# Charging_PCB.net
KiCad netlist of a schematic drawn in Altium Designer
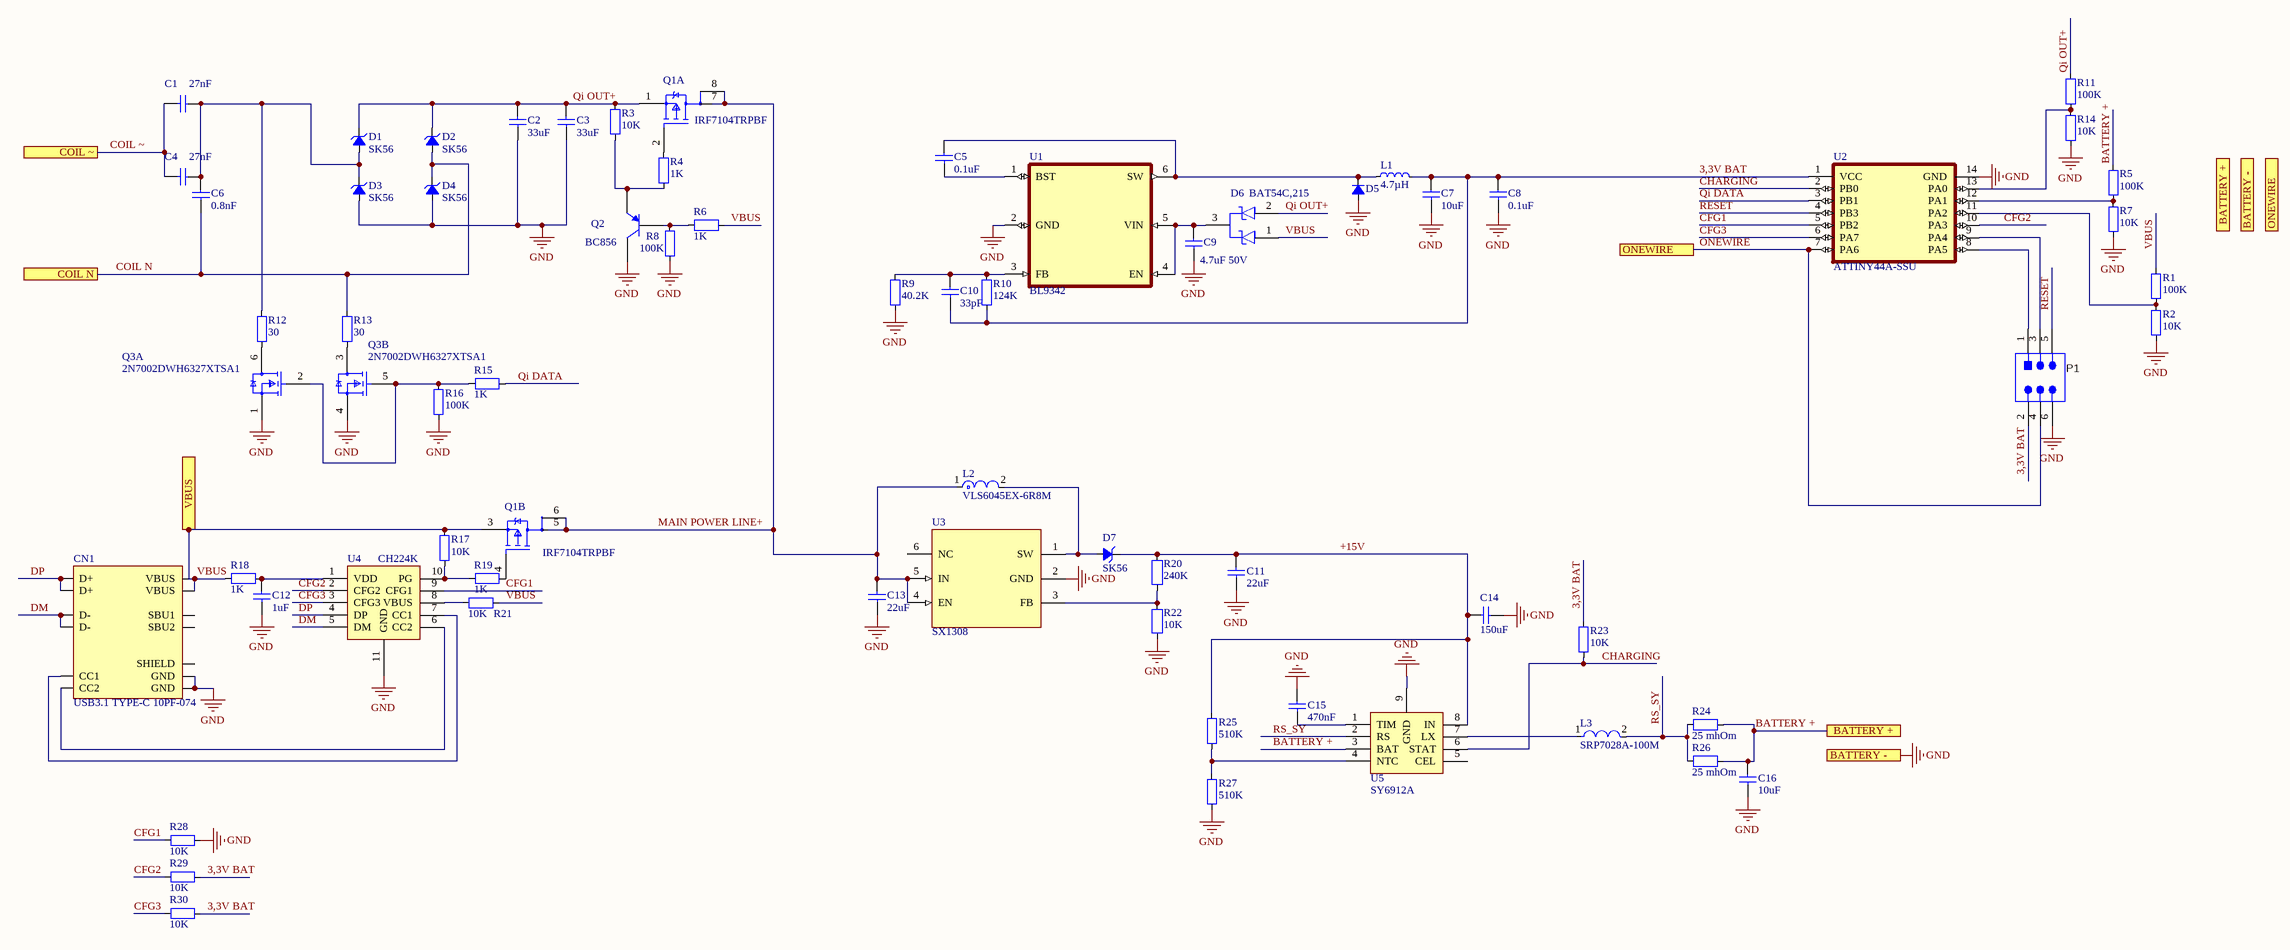
[diagram p0: Charging_PCB.SchDoc]

(export (version "E")
  (design (tool "Eeschema 10.0.6"))
  (components
    (comp (ref "C1") (value "27nF") (footprint "1206") (libsource (lib "V_NB-IoT_3.1") (part "CAP")))
    (comp (ref "C2") (value "33uF") (footprint "1206") (libsource (lib "V_NB-IoT_3.1") (part "CAP")))
    (comp (ref "C3") (value "33uF") (footprint "1206") (libsource (lib "V_NB-IoT_3.1") (part "CAP")))
    (comp (ref "C4") (value "27nF") (footprint "1206") (libsource (lib "V_NB-IoT_3.1") (part "CAP")))
    (comp (ref "C5") (value "0.1uF") (footprint "R0603") (libsource (lib "V_NB-IoT_3.1") (part "CAP")))
    (comp (ref "C6") (value "0.8nF") (footprint "1206") (libsource (lib "V_NB-IoT_3.1") (part "CAP")))
    (comp (ref "C7") (value "10uF") (footprint "C0805") (libsource (lib "V_NB-IoT_3.1") (part "CAP")))
    (comp (ref "C8") (value "0.1uF") (footprint "R0603") (libsource (lib "V_NB-IoT_3.1") (part "CAP")))
    (comp (ref "C9") (value "4.7uF 50V") (footprint "C0805") (libsource (lib "V_NB-IoT_3.1") (part "CAP")))
    (comp (ref "C10") (value "33pF") (footprint "R0603") (libsource (lib "V_NB-IoT_3.1") (part "CAP")))
    (comp (ref "C11") (value "22uF") (footprint "1206") (libsource (lib "V_NB-IoT_3.1") (part "CAP")))
    (comp (ref "C12") (value "1uF") (footprint "C0805") (libsource (lib "V_NB-IoT_3.1") (part "CAP")))
    (comp (ref "C13") (value "22uF") (footprint "1206") (libsource (lib "V_NB-IoT_3.1") (part "CAP")))
    (comp (ref "C14") (value "150uF") (footprint "1206") (libsource (lib "V_NB-IoT_3.1") (part "CAP")))
    (comp (ref "C15") (value "470nF") (footprint "R0603") (libsource (lib "V_NB-IoT_3.1") (part "CAP")))
    (comp (ref "C16") (value "10uF") (footprint "1206") (libsource (lib "V_NB-IoT_3.1") (part "CAP")))
    (comp (ref "CN1")
      (value "USB3.1 TYPE-C 10PF-074")
      (footprint "V_NB_IoT_3.1:USB3.1 TYPE-C 10PF-074")
      (description "XKB Connectivity USB-C Connector")
      (libsource (lib "V_NB-IoT_3.1") (part "USB3.1 TYPE-C 10PF-074"))
    )
    (comp (ref "D1")
      (value "SK56")
      (footprint "DO-214AA(SMB)")
      (description "DO-214 Diode")
      (fields (field (name "MANUFACTURER PART NUMBER") "China"))
      (libsource (lib "V_NB-IoT_3.1") (part "DIODE_DO-214"))
    )
    (comp (ref "D2")
      (value "SK56")
      (footprint "DO-214AA(SMB)")
      (description "DO-214 Diode")
      (fields (field (name "MANUFACTURER PART NUMBER") "China"))
      (libsource (lib "V_NB-IoT_3.1") (part "DIODE_DO-214"))
    )
    (comp (ref "D3")
      (value "SK56")
      (footprint "DO-214AA(SMB)")
      (description "DO-214 Diode")
      (fields (field (name "MANUFACTURER PART NUMBER") "China"))
      (libsource (lib "V_NB-IoT_3.1") (part "DIODE_DO-214"))
    )
    (comp (ref "D4")
      (value "SK56")
      (footprint "DO-214AA(SMB)")
      (description "DO-214 Diode")
      (fields (field (name "MANUFACTURER PART NUMBER") "China"))
      (libsource (lib "V_NB-IoT_3.1") (part "DIODE_DO-214"))
    )
    (comp (ref "D5")
      (value "~")
      (footprint "SOD-123")
      (description "Schottky diode SOD123")
      (libsource (lib "V_NB-IoT_3.1") (part "Diode_SOD123"))
    )
    (comp (ref "D6")
      (value "BAT54C,215")
      (footprint "SOT-23")
      (description "DIODE ARRAY SCHOTTKY 30V SOT23")
      (fields
        (field (name "MANUFACTURER") "Nexperia")
        (field (name "OCTOPART") "https://octopart.com/bat54c%2C215-nexperia-78738945")
      )
      (libsource (lib "V_NB-IoT_3.1") (part "BAT54C"))
    )
    (comp (ref "D7")
      (value "SK56")
      (footprint "DO-214AA(SMB)")
      (description "DO-214 Diode")
      (fields (field (name "MANUFACTURER PART NUMBER") "China"))
      (libsource (lib "V_NB-IoT_3.1") (part "DIODE_DO-214"))
    )
    (comp (ref "L1")
      (value "4.7µH")
      (footprint "INDC1608X06L")
      (description "Inductor, SMD")
      (fields
        (field (name "PART NUMBER") "L0603-10µ")
        (field (name "MANUFACTURER") "Taiyo Yuden")
        (field (name "PUBLISHER") "Nordic Semiconductor")
      )
      (libsource (lib "V_NB-IoT_3.1") (part "IND_1"))
    )
    (comp (ref "L2")
      (value "VLS6045EX-6R8M")
      (footprint "FP-VLS6045EX-100M-MFG")
      (description "FIXED IND  SMD")
      (fields (field (name "TOLERANCE") "20%"))
      (libsource (lib "V_NB-IoT_3.1") (part "VLS6045EX"))
    )
    (comp (ref "L3")
      (value "SRP7028A-100M")
      (footprint "INDUCT_7028")
      (description "FIXED IND")
      (fields (field (name "TOLERANCE") "20%") (field (name "MANUFACTURER") "Panasonic"))
      (libsource (lib "V_NB-IoT_3.1") (part "IND_SRP7028A"))
    )
    (comp (ref "P1")
      (value "TSW-103-07-G-D")
      (footprint "SMTC-TSW-103-07-G-D_V")
      (fields (field (name "MANUFACTURER") "Samtec-Inc.") (field (name "MANUFACTURER_1") "Samtec"))
      (libsource (lib "V_NB-IoT_3.1") (part "CMP-2000-07329-1"))
    )
    (comp (ref "Q1")
      (value "IRF7104TRPBF")
      (footprint "SO8")
      (description "MOSFET 2P-CH 20V 2.3A 8-SOIC")
      (libsource (lib "V_NB-IoT_3.1") (part "IRF7104TRPBF"))
    )
    (comp (ref "Q2")
      (value "BC856")
      (footprint "SOT-23")
      (description "PNP General Purpose Transistor, 65 V, -65 to 150 degC, 3-Pin SOT23, RoHS")
      (fields (field (name "MANUFACTURER") "NXP"))
      (libsource (lib "V_NB-IoT_3.1") (part "BC856"))
    )
    (comp (ref "Q3")
      (value "2N7002DWH6327XTSA1")
      (footprint "SOT363-IPC_A")
      (description "MOSFET 2N-CH 60V 0.3A SOT363")
      (libsource (lib "V_NB-IoT_3.1") (part "WM06DN03D"))
    )
    (comp (ref "R1")
      (value "100K")
      (footprint "R0603")
      (description "Resistor SMD")
      (libsource (lib "V_NB-IoT_3.1") (part "RES SMD UNI"))
    )
    (comp (ref "R2")
      (value "10K")
      (footprint "R0603")
      (description "Resistor SMD")
      (libsource (lib "V_NB-IoT_3.1") (part "RES SMD UNI"))
    )
    (comp (ref "R3")
      (value "10K")
      (footprint "R0603")
      (description "Resistor SMD")
      (libsource (lib "V_NB-IoT_3.1") (part "RES SMD UNI"))
    )
    (comp (ref "R4")
      (value "1K")
      (footprint "R0603")
      (description "Resistor SMD")
      (libsource (lib "V_NB-IoT_3.1") (part "RES SMD UNI"))
    )
    (comp (ref "R5")
      (value "100K")
      (footprint "R0603")
      (description "Resistor SMD")
      (libsource (lib "V_NB-IoT_3.1") (part "RES SMD UNI"))
    )
    (comp (ref "R6")
      (value "1K")
      (footprint "R0603")
      (description "Resistor SMD")
      (libsource (lib "V_NB-IoT_3.1") (part "RES SMD UNI"))
    )
    (comp (ref "R7")
      (value "10K")
      (footprint "R0603")
      (description "Resistor SMD")
      (libsource (lib "V_NB-IoT_3.1") (part "RES SMD UNI"))
    )
    (comp (ref "R8")
      (value "100K")
      (footprint "R0603")
      (description "Resistor SMD")
      (libsource (lib "V_NB-IoT_3.1") (part "RES SMD UNI"))
    )
    (comp (ref "R9")
      (value "40.2K")
      (footprint "R0603")
      (description "Resistor SMD")
      (libsource (lib "V_NB-IoT_3.1") (part "RES SMD UNI"))
    )
    (comp (ref "R10")
      (value "124K")
      (footprint "R0603")
      (description "Resistor SMD")
      (libsource (lib "V_NB-IoT_3.1") (part "RES SMD UNI"))
    )
    (comp (ref "R11")
      (value "100K")
      (footprint "R0603")
      (description "Resistor SMD")
      (libsource (lib "V_NB-IoT_3.1") (part "RES SMD UNI"))
    )
    (comp (ref "R12")
      (value "30")
      (footprint "R0603")
      (description "Resistor SMD")
      (libsource (lib "V_NB-IoT_3.1") (part "RES SMD UNI"))
    )
    (comp (ref "R13")
      (value "30")
      (footprint "R0603")
      (description "Resistor SMD")
      (libsource (lib "V_NB-IoT_3.1") (part "RES SMD UNI"))
    )
    (comp (ref "R14")
      (value "10K")
      (footprint "R0603")
      (description "Resistor SMD")
      (libsource (lib "V_NB-IoT_3.1") (part "RES SMD UNI"))
    )
    (comp (ref "R15")
      (value "1K")
      (footprint "R0603")
      (description "Resistor SMD")
      (libsource (lib "V_NB-IoT_3.1") (part "RES SMD UNI"))
    )
    (comp (ref "R16")
      (value "100K")
      (footprint "R0603")
      (description "Resistor SMD")
      (libsource (lib "V_NB-IoT_3.1") (part "RES SMD UNI"))
    )
    (comp (ref "R17")
      (value "10K")
      (footprint "R0603")
      (description "Resistor SMD")
      (libsource (lib "V_NB-IoT_3.1") (part "RES SMD UNI"))
    )
    (comp (ref "R18")
      (value "1K")
      (footprint "R0603")
      (description "Resistor SMD")
      (libsource (lib "V_NB-IoT_3.1") (part "RES SMD UNI"))
    )
    (comp (ref "R19")
      (value "1K")
      (footprint "R0603")
      (description "Resistor SMD")
      (libsource (lib "V_NB-IoT_3.1") (part "RES SMD UNI"))
    )
    (comp (ref "R20")
      (value "240K")
      (footprint "R0603")
      (description "Resistor SMD")
      (libsource (lib "V_NB-IoT_3.1") (part "RES SMD UNI"))
    )
    (comp (ref "R21")
      (value "10K")
      (footprint "R0603")
      (description "Resistor SMD")
      (libsource (lib "V_NB-IoT_3.1") (part "RES SMD UNI"))
    )
    (comp (ref "R22")
      (value "10K")
      (footprint "R0603")
      (description "Resistor SMD")
      (libsource (lib "V_NB-IoT_3.1") (part "RES SMD UNI"))
    )
    (comp (ref "R23")
      (value "10K")
      (footprint "R0603")
      (description "Resistor SMD")
      (libsource (lib "V_NB-IoT_3.1") (part "RES SMD UNI"))
    )
    (comp (ref "R24")
      (value "25 mhOm")
      (footprint "1206")
      (description "Resistor SMD")
      (libsource (lib "V_NB-IoT_3.1") (part "RES SMD UNI"))
    )
    (comp (ref "R25")
      (value "510K")
      (footprint "R0603")
      (description "Resistor SMD")
      (libsource (lib "V_NB-IoT_3.1") (part "RES SMD UNI"))
    )
    (comp (ref "R26")
      (value "25 mhOm")
      (footprint "1206")
      (description "Resistor SMD")
      (libsource (lib "V_NB-IoT_3.1") (part "RES SMD UNI"))
    )
    (comp (ref "R27")
      (value "510K")
      (footprint "R0603")
      (description "Resistor SMD")
      (libsource (lib "V_NB-IoT_3.1") (part "RES SMD UNI"))
    )
    (comp (ref "R28")
      (value "10K")
      (footprint "R0603")
      (description "Resistor SMD")
      (libsource (lib "V_NB-IoT_3.1") (part "RES SMD UNI"))
    )
    (comp (ref "R29")
      (value "10K")
      (footprint "R0603")
      (description "Resistor SMD")
      (libsource (lib "V_NB-IoT_3.1") (part "RES SMD UNI"))
    )
    (comp (ref "R30")
      (value "10K")
      (footprint "R0603")
      (description "Resistor SMD")
      (libsource (lib "V_NB-IoT_3.1") (part "RES SMD UNI"))
    )
    (comp (ref "U1")
      (value "BL9342")
      (footprint "SOT23-6")
      (fields (field (name "MF") "{'manufacturer': u'Texas Instruments'}"))
      (libsource (lib "V_NB-IoT_3.1") (part "BL9342"))
    )
    (comp (ref "U2")
      (value "ATTINY44A-SSU")
      (footprint "SO14")
      (fields (field (name "MF") "{'manufacturer': u'Microchip'}"))
      (libsource (lib "V_NB-IoT_3.1") (part "ATTINY44A-SSU"))
    )
    (comp (ref "U3")
      (value "SX1308")
      (footprint "SOT23-6")
      (description "IC REG BOOST ADJ 2A TSOT23-6")
      (fields (field (name "MANUFACTURER") "Suosemi"))
      (libsource (lib "V_NB-IoT_3.1") (part "SX1308"))
    )
    (comp (ref "U4")
      (value "CH224K")
      (footprint "ESSOP10")
      (description "IC PD QC USB driver")
      (fields (field (name "MANUFACTURER") "ST") (field (name "MANUFACTURER PART NUMBER") "ST3485EBDR"))
      (libsource (lib "V_NB-IoT_3.1") (part "CH224K"))
    )
    (comp (ref "U5") (value "SY6912A") (footprint "PSOP8") (libsource (lib "V_NB-IoT_3.1") (part "SY6912A")))
  )
  (nets
    (net (code "1") (name "/+15V") (class "Default")
      (node (ref "C11") (pin "2") (pinfunction "2_2") (pintype "passive"))
      (node (ref "C14") (pin "1") (pinfunction "1_1") (pintype "passive"))
      (node (ref "D7") (pin "1") (pinfunction "K_1") (pintype "passive"))
      (node (ref "R20") (pin "1") (pinfunction "1_1") (pintype "passive"))
      (node (ref "R25") (pin "1") (pinfunction "1_1") (pintype "passive"))
      (node (ref "U5") (pin "8") (pinfunction "IN_8") (pintype "passive"))
    )
    (net (code "2") (name "/3,3V BAT") (class "Default")
      (node (ref "C10") (pin "1") (pinfunction "1_1") (pintype "passive"))
      (node (ref "C7") (pin "2") (pinfunction "2_2") (pintype "passive"))
      (node (ref "C8") (pin "2") (pinfunction "2_2") (pintype "passive"))
      (node (ref "L1") (pin "2") (pinfunction "2_2") (pintype "passive"))
      (node (ref "P1") (pin "2") (pinfunction "2_2") (pintype "passive"))
      (node (ref "R10") (pin "1") (pinfunction "1_1") (pintype "passive"))
      (node (ref "R23") (pin "2") (pinfunction "2_2") (pintype "passive"))
      (node (ref "R29") (pin "2") (pinfunction "2_2") (pintype "passive"))
      (node (ref "R30") (pin "2") (pinfunction "2_2") (pintype "passive"))
      (node (ref "U2") (pin "1") (pinfunction "VCC_1") (pintype "power_in"))
    )
    (net (code "3") (name "/BATTERY +") (class "Default")
      (node (ref "C16") (pin "2") (pinfunction "2_2") (pintype "passive"))
      (node (ref "R24") (pin "2") (pinfunction "2_2") (pintype "passive"))
      (node (ref "R26") (pin "2") (pinfunction "2_2") (pintype "passive"))
      (node (ref "R5") (pin "2") (pinfunction "2_2") (pintype "passive"))
      (node (ref "U5") (pin "3") (pinfunction "BAT_3") (pintype "passive"))
    )
    (net (code "4") (name "/CFG1") (class "Default")
      (node (ref "R28") (pin "1") (pinfunction "1_1") (pintype "passive"))
      (node (ref "U2") (pin "5") (pinfunction "PB2_5") (pintype "bidirectional"))
      (node (ref "U4") (pin "9") (pinfunction "CFG1_9") (pintype "power_in"))
    )
    (net (code "5") (name "/CFG2") (class "Default")
      (node (ref "R29") (pin "1") (pinfunction "1_1") (pintype "passive"))
      (node (ref "U2") (pin "10") (pinfunction "PA3_10") (pintype "bidirectional"))
      (node (ref "U4") (pin "2") (pinfunction "CFG2_2") (pintype "power_in"))
    )
    (net (code "6") (name "/CFG3") (class "Default")
      (node (ref "R30") (pin "1") (pinfunction "1_1") (pintype "passive"))
      (node (ref "U2") (pin "6") (pinfunction "PA7_6") (pintype "bidirectional"))
      (node (ref "U4") (pin "3") (pinfunction "CFG3_3") (pintype "power_in"))
    )
    (net (code "7") (name "/CHARGING") (class "Default")
      (node (ref "R23") (pin "1") (pinfunction "1_1") (pintype "passive"))
      (node (ref "U2") (pin "2") (pinfunction "PB0_2") (pintype "bidirectional"))
      (node (ref "U5") (pin "6") (pinfunction "STAT_6") (pintype "passive"))
    )
    (net (code "8") (name "/COIL N") (class "Default")
      (node (ref "C6") (pin "2") (pinfunction "2_2") (pintype "passive"))
      (node (ref "D2") (pin "2") (pinfunction "A_2") (pintype "passive"))
      (node (ref "D4") (pin "1") (pinfunction "K_1") (pintype "passive"))
      (node (ref "R13") (pin "2") (pinfunction "2_2") (pintype "passive"))
    )
    (net (code "9") (name "/COIL ~") (class "Default")
      (node (ref "C1") (pin "2") (pinfunction "2_2") (pintype "passive"))
      (node (ref "C4") (pin "2") (pinfunction "2_2") (pintype "passive"))
    )
    (net (code "10") (name "/DM") (class "Default")
      (node (ref "CN1") (pin "6") (pinfunction "D-_6") (pintype "passive"))
      (node (ref "CN1") (pin "9") (pinfunction "D-_9") (pintype "passive"))
      (node (ref "U4") (pin "5") (pinfunction "DM_5") (pintype "power_in"))
    )
    (net (code "11") (name "/DP") (class "Default")
      (node (ref "CN1") (pin "4") (pinfunction "D+_4") (pintype "passive"))
      (node (ref "CN1") (pin "7") (pinfunction "D+_7") (pintype "passive"))
      (node (ref "U4") (pin "4") (pinfunction "DP_4") (pintype "power_in"))
    )
    (net (code "12") (name "/MAIN POWER LINE+") (class "Default")
      (node (ref "C13") (pin "2") (pinfunction "2_2") (pintype "passive"))
      (node (ref "L2") (pin "1") (pinfunction "1_1") (pintype "passive"))
      (node (ref "Q1") (pin "5") (pinfunction "D2_5") (pintype "passive"))
      (node (ref "Q1") (pin "6") (pinfunction "D2_6") (pintype "passive"))
      (node (ref "Q1") (pin "7") (pinfunction "D1_7") (pintype "passive"))
      (node (ref "Q1") (pin "8") (pinfunction "D1_8") (pintype "passive"))
      (node (ref "U3") (pin "4") (pinfunction "EN_4") (pintype "input"))
      (node (ref "U3") (pin "5") (pinfunction "IN_5") (pintype "input"))
    )
    (net (code "13") (name "/ONEWIRE") (class "Default")
      (node (ref "P1") (pin "4") (pinfunction "4_4") (pintype "passive"))
      (node (ref "U2") (pin "7") (pinfunction "PA6_7") (pintype "bidirectional"))
    )
    (net (code "14") (name "/Qi DATA") (class "Default")
      (node (ref "R15") (pin "2") (pinfunction "2_2") (pintype "passive"))
      (node (ref "U2") (pin "3") (pinfunction "PB1_3") (pintype "bidirectional"))
    )
    (net (code "15") (name "/Qi OUT+") (class "Default")
      (node (ref "C2") (pin "1") (pinfunction "1_1") (pintype "passive"))
      (node (ref "C3") (pin "1") (pinfunction "1_1") (pintype "passive"))
      (node (ref "D1") (pin "1") (pinfunction "K_1") (pintype "passive"))
      (node (ref "D2") (pin "1") (pinfunction "K_1") (pintype "passive"))
      (node (ref "D6") (pin "2") (pinfunction "2_ANODE_2") (pintype "passive"))
      (node (ref "Q1") (pin "1") (pinfunction "S1_1") (pintype "passive"))
      (node (ref "R11") (pin "2") (pinfunction "2_2") (pintype "passive"))
      (node (ref "R3") (pin "2") (pinfunction "2_2") (pintype "passive"))
    )
    (net (code "16") (name "/RESET") (class "Default")
      (node (ref "P1") (pin "5") (pinfunction "5_5") (pintype "passive"))
      (node (ref "U2") (pin "4") (pinfunction "PB3_4") (pintype "bidirectional"))
    )
    (net (code "17") (name "/RS_SY") (class "Default")
      (node (ref "L3") (pin "2") (pinfunction "2_2") (pintype "passive"))
      (node (ref "R24") (pin "1") (pinfunction "1_1") (pintype "passive"))
      (node (ref "R26") (pin "1") (pinfunction "1_1") (pintype "passive"))
      (node (ref "U5") (pin "2") (pinfunction "RS_2") (pintype "passive"))
    )
    (net (code "18") (name "/VBUS") (class "Default")
      (node (ref "CN1") (pin "10") (pinfunction "VBUS_10") (pintype "power_in"))
      (node (ref "CN1") (pin "3") (pinfunction "VBUS_3") (pintype "power_in"))
      (node (ref "D6") (pin "1") (pinfunction "1_ANODE_1") (pintype "passive"))
      (node (ref "Q1") (pin "3") (pinfunction "S2_3") (pintype "passive"))
      (node (ref "R1") (pin "2") (pinfunction "2_2") (pintype "passive"))
      (node (ref "R17") (pin "2") (pinfunction "2_2") (pintype "passive"))
      (node (ref "R18") (pin "1") (pinfunction "1_1") (pintype "passive"))
      (node (ref "R21") (pin "2") (pinfunction "2_2") (pintype "passive"))
      (node (ref "R6") (pin "2") (pinfunction "2_2") (pintype "passive"))
    )
    (net (code "19") (name "GND") (class "Default")
      (node (ref "C11") (pin "1") (pinfunction "1_1") (pintype "passive"))
      (node (ref "C12") (pin "1") (pinfunction "1_1") (pintype "passive"))
      (node (ref "C13") (pin "1") (pinfunction "1_1") (pintype "passive"))
      (node (ref "C14") (pin "2") (pinfunction "2_2") (pintype "passive"))
      (node (ref "C15") (pin "2") (pinfunction "2_2") (pintype "passive"))
      (node (ref "C16") (pin "1") (pinfunction "1_1") (pintype "passive"))
      (node (ref "C2") (pin "2") (pinfunction "2_2") (pintype "passive"))
      (node (ref "C3") (pin "2") (pinfunction "2_2") (pintype "passive"))
      (node (ref "C7") (pin "1") (pinfunction "1_1") (pintype "passive"))
      (node (ref "C8") (pin "1") (pinfunction "1_1") (pintype "passive"))
      (node (ref "C9") (pin "1") (pinfunction "1_1") (pintype "passive"))
      (node (ref "CN1") (pin "1") (pinfunction "GND_1") (pintype "passive"))
      (node (ref "CN1") (pin "12") (pinfunction "GND_12") (pintype "power_in"))
      (node (ref "D3") (pin "2") (pinfunction "A_2") (pintype "passive"))
      (node (ref "D4") (pin "2") (pinfunction "A_2") (pintype "passive"))
      (node (ref "D5") (pin "1") (pinfunction "A_1") (pintype "passive"))
      (node (ref "P1") (pin "6") (pinfunction "6_6") (pintype "passive"))
      (node (ref "Q2") (pin "3") (pinfunction "C_3") (pintype "passive"))
      (node (ref "Q3") (pin "1") (pinfunction "S1_1") (pintype "passive"))
      (node (ref "Q3") (pin "4") (pinfunction "S2_4") (pintype "passive"))
      (node (ref "R14") (pin "1") (pinfunction "1_1") (pintype "passive"))
      (node (ref "R16") (pin "1") (pinfunction "1_1") (pintype "passive"))
      (node (ref "R2") (pin "1") (pinfunction "1_1") (pintype "passive"))
      (node (ref "R22") (pin "1") (pinfunction "1_1") (pintype "passive"))
      (node (ref "R27") (pin "2") (pinfunction "2_2") (pintype "passive"))
      (node (ref "R28") (pin "2") (pinfunction "2_2") (pintype "passive"))
      (node (ref "R7") (pin "1") (pinfunction "1_1") (pintype "passive"))
      (node (ref "R8") (pin "1") (pinfunction "1_1") (pintype "passive"))
      (node (ref "R9") (pin "1") (pinfunction "1_1") (pintype "passive"))
      (node (ref "U1") (pin "2") (pinfunction "GND_2") (pintype "bidirectional"))
      (node (ref "U2") (pin "14") (pinfunction "GND_14") (pintype "power_in"))
      (node (ref "U3") (pin "2") (pinfunction "GND_2") (pintype "passive"))
      (node (ref "U4") (pin "11") (pinfunction "GND_11") (pintype "passive"))
      (node (ref "U5") (pin "9") (pinfunction "GND_9") (pintype "passive"))
    )
    (net (code "20") (name "Net-(CN1-CC1)") (class "Default")
      (node (ref "CN1") (pin "2") (pinfunction "CC1_2") (pintype "passive"))
      (node (ref "U4") (pin "7") (pinfunction "CC1_7") (pintype "power_in"))
    )
    (net (code "21") (name "Net-(CN1-CC2)") (class "Default")
      (node (ref "CN1") (pin "8") (pinfunction "CC2_8") (pintype "passive"))
      (node (ref "U4") (pin "6") (pinfunction "CC2_6") (pintype "power_in"))
    )
    (net (code "22") (name "Net-(D1-A)") (class "Default")
      (node (ref "C1") (pin "1") (pinfunction "1_1") (pintype "passive"))
      (node (ref "C4") (pin "1") (pinfunction "1_1") (pintype "passive"))
      (node (ref "C6") (pin "1") (pinfunction "1_1") (pintype "passive"))
      (node (ref "D1") (pin "2") (pinfunction "A_2") (pintype "passive"))
      (node (ref "D3") (pin "1") (pinfunction "K_1") (pintype "passive"))
      (node (ref "R12") (pin "2") (pinfunction "2_2") (pintype "passive"))
    )
    (net (code "23") (name "Net-(D5-K)") (class "Default")
      (node (ref "C5") (pin "2") (pinfunction "2_2") (pintype "passive"))
      (node (ref "D5") (pin "2") (pinfunction "K_2") (pintype "passive"))
      (node (ref "L1") (pin "1") (pinfunction "1_1") (pintype "passive"))
      (node (ref "U1") (pin "6") (pinfunction "SW_6") (pintype "output"))
    )
    (net (code "24") (name "Net-(D6-COMMON_CATHODE)") (class "Default")
      (node (ref "C9") (pin "2") (pinfunction "2_2") (pintype "passive"))
      (node (ref "D6") (pin "3") (pinfunction "COMMON_CATHODE_3") (pintype "passive"))
      (node (ref "U1") (pin "4") (pinfunction "EN_4") (pintype "input"))
      (node (ref "U1") (pin "5") (pinfunction "VIN_5") (pintype "input"))
    )
    (net (code "25") (name "Net-(D7-A)") (class "Default")
      (node (ref "D7") (pin "2") (pinfunction "A_2") (pintype "passive"))
      (node (ref "L2") (pin "2") (pinfunction "2_2") (pintype "passive"))
      (node (ref "U3") (pin "1") (pinfunction "SW_1") (pintype "power_in"))
    )
    (net (code "26") (name "Net-(Q1A-G1)") (class "Default")
      (node (ref "Q1") (pin "2") (pinfunction "G1_2") (pintype "passive"))
      (node (ref "R4") (pin "2") (pinfunction "2_2") (pintype "passive"))
    )
    (net (code "27") (name "Net-(Q1B-G2)") (class "Default")
      (node (ref "Q1") (pin "4") (pinfunction "G2_4") (pintype "passive"))
      (node (ref "R19") (pin "2") (pinfunction "2_2") (pintype "passive"))
    )
    (net (code "28") (name "Net-(Q2-B)") (class "Default")
      (node (ref "Q2") (pin "1") (pinfunction "B_1") (pintype "passive"))
      (node (ref "R6") (pin "1") (pinfunction "1_1") (pintype "passive"))
      (node (ref "R8") (pin "2") (pinfunction "2_2") (pintype "passive"))
    )
    (net (code "29") (name "Net-(Q2-E)") (class "Default")
      (node (ref "Q2") (pin "2") (pinfunction "E_2") (pintype "passive"))
      (node (ref "R3") (pin "1") (pinfunction "1_1") (pintype "passive"))
      (node (ref "R4") (pin "1") (pinfunction "1_1") (pintype "passive"))
    )
    (net (code "30") (name "Net-(Q3A-D1)") (class "Default")
      (node (ref "Q3") (pin "6") (pinfunction "D1_6") (pintype "passive"))
      (node (ref "R12") (pin "1") (pinfunction "1_1") (pintype "passive"))
    )
    (net (code "31") (name "Net-(Q3A-G1)") (class "Default")
      (node (ref "Q3") (pin "2") (pinfunction "G1_2") (pintype "passive"))
      (node (ref "Q3") (pin "5") (pinfunction "G2_5") (pintype "passive"))
      (node (ref "R15") (pin "1") (pinfunction "1_1") (pintype "passive"))
      (node (ref "R16") (pin "2") (pinfunction "2_2") (pintype "passive"))
    )
    (net (code "32") (name "Net-(Q3B-D2)") (class "Default")
      (node (ref "Q3") (pin "3") (pinfunction "D2_3") (pintype "passive"))
      (node (ref "R13") (pin "1") (pinfunction "1_1") (pintype "passive"))
    )
    (net (code "33") (name "Net-(U1-BST)") (class "Default")
      (node (ref "C5") (pin "1") (pinfunction "1_1") (pintype "passive"))
      (node (ref "U1") (pin "1") (pinfunction "BST_1") (pintype "bidirectional"))
    )
    (net (code "34") (name "Net-(U1-FB)") (class "Default")
      (node (ref "C10") (pin "2") (pinfunction "2_2") (pintype "passive"))
      (node (ref "R10") (pin "2") (pinfunction "2_2") (pintype "passive"))
      (node (ref "R9") (pin "2") (pinfunction "2_2") (pintype "passive"))
      (node (ref "U1") (pin "3") (pinfunction "FB_3") (pintype "input"))
    )
    (net (code "35") (name "Net-(U2-PA0)") (class "Default")
      (node (ref "R11") (pin "1") (pinfunction "1_1") (pintype "passive"))
      (node (ref "R14") (pin "2") (pinfunction "2_2") (pintype "passive"))
      (node (ref "U2") (pin "13") (pinfunction "PA0_13") (pintype "bidirectional"))
    )
    (net (code "36") (name "Net-(U2-PA1)") (class "Default")
      (node (ref "R5") (pin "1") (pinfunction "1_1") (pintype "passive"))
      (node (ref "R7") (pin "2") (pinfunction "2_2") (pintype "passive"))
      (node (ref "U2") (pin "12") (pinfunction "PA1_12") (pintype "bidirectional"))
    )
    (net (code "37") (name "Net-(U2-PA2)") (class "Default")
      (node (ref "R1") (pin "1") (pinfunction "1_1") (pintype "passive"))
      (node (ref "R2") (pin "2") (pinfunction "2_2") (pintype "passive"))
      (node (ref "U2") (pin "11") (pinfunction "PA2_11") (pintype "bidirectional"))
    )
    (net (code "38") (name "Net-(U2-PA4)") (class "Default")
      (node (ref "P1") (pin "3") (pinfunction "3_3") (pintype "passive"))
      (node (ref "U2") (pin "9") (pinfunction "PA4_9") (pintype "bidirectional"))
    )
    (net (code "39") (name "Net-(U2-PA5)") (class "Default")
      (node (ref "P1") (pin "1") (pinfunction "1_1") (pintype "passive"))
      (node (ref "U2") (pin "8") (pinfunction "PA5_8") (pintype "bidirectional"))
    )
    (net (code "40") (name "Net-(U3-FB)") (class "Default")
      (node (ref "R20") (pin "2") (pinfunction "2_2") (pintype "passive"))
      (node (ref "R22") (pin "2") (pinfunction "2_2") (pintype "passive"))
      (node (ref "U3") (pin "3") (pinfunction "FB_3") (pintype "power_in"))
    )
    (net (code "41") (name "Net-(U4-PG)") (class "Default")
      (node (ref "R17") (pin "1") (pinfunction "1_1") (pintype "passive"))
      (node (ref "R19") (pin "1") (pinfunction "1_1") (pintype "passive"))
      (node (ref "U4") (pin "10") (pinfunction "PG_10") (pintype "power_in"))
    )
    (net (code "42") (name "Net-(U4-VBUS)") (class "Default")
      (node (ref "R21") (pin "1") (pinfunction "1_1") (pintype "passive"))
      (node (ref "U4") (pin "8") (pinfunction "VBUS_8") (pintype "power_in"))
    )
    (net (code "43") (name "Net-(U4-VDD)") (class "Default")
      (node (ref "C12") (pin "2") (pinfunction "2_2") (pintype "passive"))
      (node (ref "R18") (pin "2") (pinfunction "2_2") (pintype "passive"))
      (node (ref "U4") (pin "1") (pinfunction "VDD_1") (pintype "power_in"))
    )
    (net (code "44") (name "Net-(U5-LX)") (class "Default")
      (node (ref "L3") (pin "1") (pinfunction "1_1") (pintype "passive"))
      (node (ref "U5") (pin "7") (pinfunction "LX_7") (pintype "passive"))
    )
    (net (code "45") (name "Net-(U5-NTC)") (class "Default")
      (node (ref "R25") (pin "2") (pinfunction "2_2") (pintype "passive"))
      (node (ref "R27") (pin "1") (pinfunction "1_1") (pintype "passive"))
      (node (ref "U5") (pin "4") (pinfunction "NTC_4") (pintype "passive"))
    )
    (net (code "46") (name "Net-(U5-TIM)") (class "Default")
      (node (ref "C15") (pin "1") (pinfunction "1_1") (pintype "passive"))
      (node (ref "U5") (pin "1") (pinfunction "TIM_1") (pintype "passive"))
    )
    (net (code "47") (name "unconnected-(CN1-SBU1-Pad11)") (class "Default")
      (node (ref "CN1") (pin "11") (pinfunction "SBU1_11") (pintype "passive"))
    )
    (net (code "48") (name "unconnected-(CN1-SBU2-Pad5)") (class "Default")
      (node (ref "CN1") (pin "5") (pinfunction "SBU2_5") (pintype "passive"))
    )
    (net (code "49") (name "unconnected-(CN1-SHIELD-PadMH)") (class "Default")
      (node (ref "CN1") (pin "MH") (pinfunction "SHIELD_MH") (pintype "passive"))
    )
    (net (code "50") (name "unconnected-(U3-NC-Pad6)") (class "Default")
      (node (ref "U3") (pin "6") (pinfunction "NC_6") (pintype "passive"))
    )
    (net (code "51") (name "unconnected-(U5-CEL-Pad5)") (class "Default")
      (node (ref "U5") (pin "5") (pinfunction "CEL_5") (pintype "passive"))
    )
  )
)
